# MA_interface-board.net
KiCad netlist of a schematic drawn in EAGLE
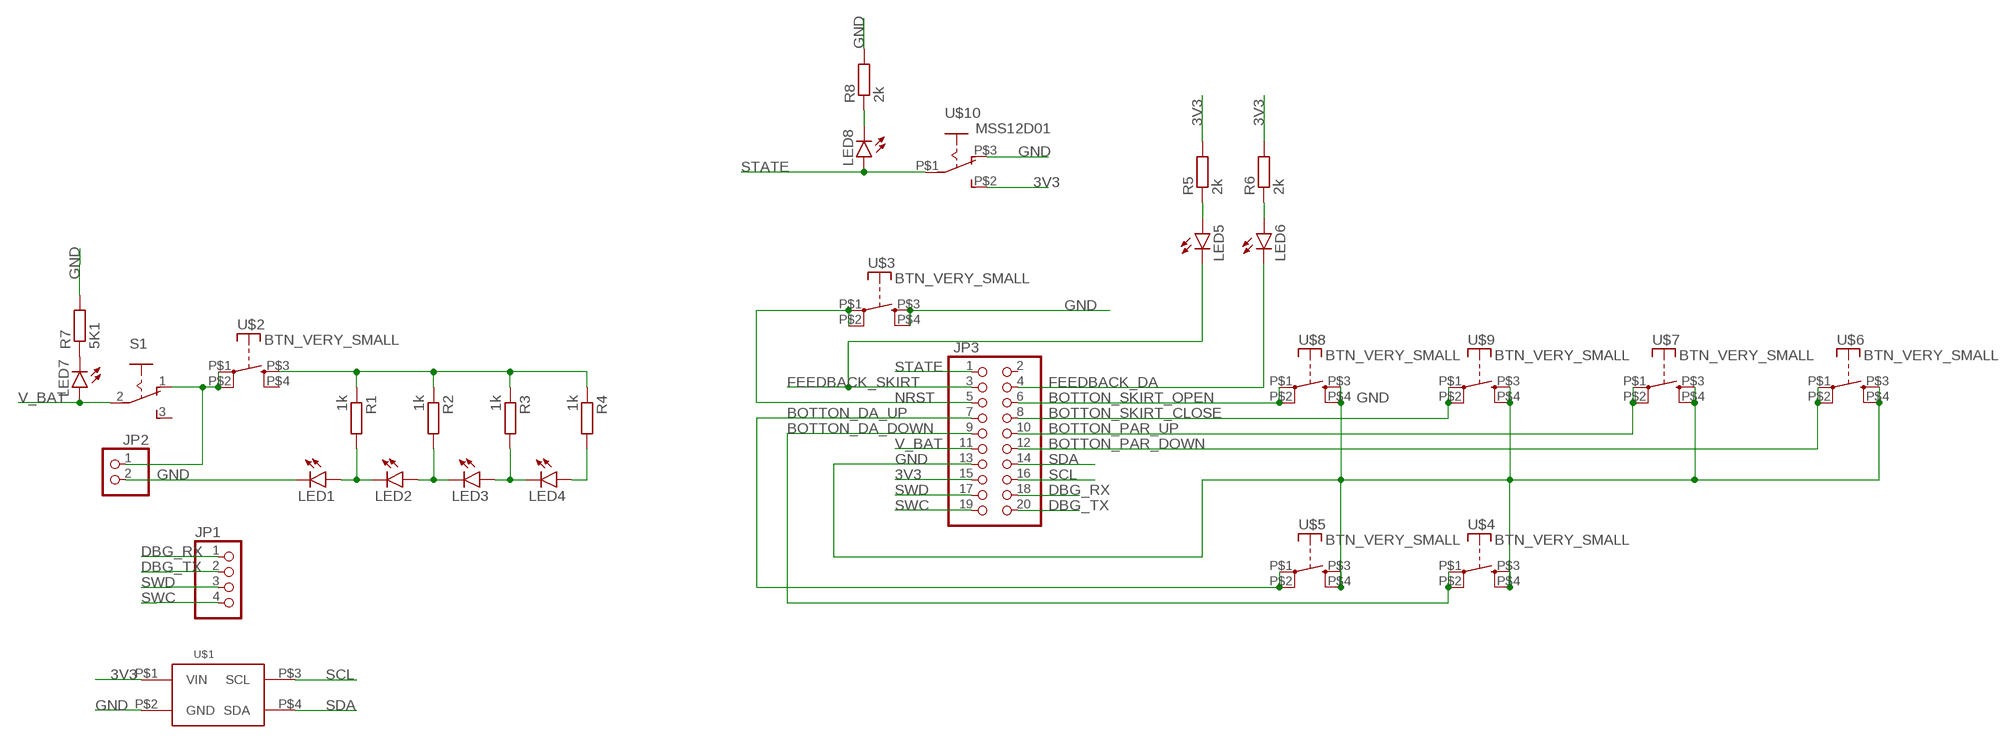
[diagram p0: schematic, sheet 1]

(export (version "E")
  (design (tool "Eeschema 10.0.6"))
  (components
    (comp (ref "JP1")
      (value "PINHD-1X4")
      (footprint "eagle-import:1X04")
      (libsource (lib "eagle-import") (part "PINHD-1X4"))
    )
    (comp (ref "JP2")
      (value "PINHD-1X2")
      (footprint "eagle-import:1X02")
      (libsource (lib "eagle-import") (part "PINHD-1X2"))
    )
    (comp (ref "JP3")
      (value "PINHD-2X10")
      (footprint "eagle-import:2X10")
      (libsource (lib "eagle-import") (part "PINHD-2X10"))
    )
    (comp (ref "LED1")
      (value "LEDSML0603")
      (footprint "eagle-import:SML0603")
      (libsource (lib "eagle-import") (part "LEDSML0603"))
    )
    (comp (ref "LED2")
      (value "LEDSML0603")
      (footprint "eagle-import:SML0603")
      (libsource (lib "eagle-import") (part "LEDSML0603"))
    )
    (comp (ref "LED3")
      (value "LEDSML0603")
      (footprint "eagle-import:SML0603")
      (libsource (lib "eagle-import") (part "LEDSML0603"))
    )
    (comp (ref "LED4")
      (value "LEDSML0603")
      (footprint "eagle-import:SML0603")
      (libsource (lib "eagle-import") (part "LEDSML0603"))
    )
    (comp (ref "LED5")
      (value "LEDSML0603")
      (footprint "eagle-import:SML0603")
      (libsource (lib "eagle-import") (part "LEDSML0603"))
    )
    (comp (ref "LED6")
      (value "LEDSML0603")
      (footprint "eagle-import:SML0603")
      (libsource (lib "eagle-import") (part "LEDSML0603"))
    )
    (comp (ref "LED7")
      (value "LEDSML0603")
      (footprint "eagle-import:SML0603")
      (libsource (lib "eagle-import") (part "LEDSML0603"))
    )
    (comp (ref "LED8")
      (value "LEDSML0603")
      (footprint "eagle-import:SML0603")
      (libsource (lib "eagle-import") (part "LEDSML0603"))
    )
    (comp (ref "R1")
      (value "1k")
      (footprint "eagle-import:R0603")
      (libsource (lib "eagle-import") (part "R-EU_R0603"))
    )
    (comp (ref "R2")
      (value "1k")
      (footprint "eagle-import:R0603")
      (libsource (lib "eagle-import") (part "R-EU_R0603"))
    )
    (comp (ref "R3")
      (value "1k")
      (footprint "eagle-import:R0603")
      (libsource (lib "eagle-import") (part "R-EU_R0603"))
    )
    (comp (ref "R4")
      (value "1k")
      (footprint "eagle-import:R0603")
      (libsource (lib "eagle-import") (part "R-EU_R0603"))
    )
    (comp (ref "R5")
      (value "2k")
      (footprint "eagle-import:R0603")
      (libsource (lib "eagle-import") (part "R-EU_R0603"))
    )
    (comp (ref "R6")
      (value "2k")
      (footprint "eagle-import:R0603")
      (libsource (lib "eagle-import") (part "R-EU_R0603"))
    )
    (comp (ref "R7")
      (value "5K1")
      (footprint "eagle-import:R0603")
      (libsource (lib "eagle-import") (part "R-EU_R0603"))
    )
    (comp (ref "R8")
      (value "2k")
      (footprint "eagle-import:R0603")
      (libsource (lib "eagle-import") (part "R-EU_R0603"))
    )
    (comp (ref "S1")
      (value "UNICS-SWITCH")
      (footprint "eagle-import:UNICS-SWITCH")
      (libsource (lib "eagle-import") (part "UNICS-SWITCH"))
    )
    (comp (ref "U$1")
      (value "BME280BME280-PINS-ONLY")
      (footprint "eagle-import:BME280-PINS-ONLY")
      (libsource (lib "eagle-import") (part "BME280BME280-PINS-ONLY"))
    )
    (comp (ref "U$2")
      (value "BTN_VERY_SMALL")
      (footprint "eagle-import:BTN_VERY_SMALL")
      (libsource (lib "eagle-import") (part "BTN_VERY_SMALL"))
    )
    (comp (ref "U$3")
      (value "BTN_VERY_SMALL")
      (footprint "eagle-import:BTN_VERY_SMALL")
      (libsource (lib "eagle-import") (part "BTN_VERY_SMALL"))
    )
    (comp (ref "U$4")
      (value "BTN_VERY_SMALL")
      (footprint "eagle-import:BTN_VERY_SMALL")
      (libsource (lib "eagle-import") (part "BTN_VERY_SMALL"))
    )
    (comp (ref "U$5")
      (value "BTN_VERY_SMALL")
      (footprint "eagle-import:BTN_VERY_SMALL")
      (libsource (lib "eagle-import") (part "BTN_VERY_SMALL"))
    )
    (comp (ref "U$6")
      (value "BTN_VERY_SMALL")
      (footprint "eagle-import:BTN_VERY_SMALL")
      (libsource (lib "eagle-import") (part "BTN_VERY_SMALL"))
    )
    (comp (ref "U$7")
      (value "BTN_VERY_SMALL")
      (footprint "eagle-import:BTN_VERY_SMALL")
      (libsource (lib "eagle-import") (part "BTN_VERY_SMALL"))
    )
    (comp (ref "U$8")
      (value "BTN_VERY_SMALL")
      (footprint "eagle-import:BTN_VERY_SMALL")
      (libsource (lib "eagle-import") (part "BTN_VERY_SMALL"))
    )
    (comp (ref "U$9")
      (value "BTN_VERY_SMALL")
      (footprint "eagle-import:BTN_VERY_SMALL")
      (libsource (lib "eagle-import") (part "BTN_VERY_SMALL"))
    )
    (comp (ref "U$10")
      (value "MSS12D01")
      (footprint "eagle-import:MSS12D01")
      (libsource (lib "eagle-import") (part "MSS12D01"))
    )
  )
  (nets
    (net (code "1") (name "/3V3") (class "Default")
      (node (ref "JP3") (pin "15") (pinfunction "15_15") (pintype "passive"))
      (node (ref "R5") (pin "2") (pinfunction "2_2") (pintype "passive"))
      (node (ref "R6") (pin "2") (pinfunction "2_2") (pintype "passive"))
      (node (ref "U$1") (pin "P$1") (pinfunction "VIN_P$1") (pintype "bidirectional"))
      (node (ref "U$10") (pin "P$2") (pinfunction "S_P$2") (pintype "passive"))
    )
    (net (code "2") (name "/BOTTON_DA_DOWN") (class "Default")
      (node (ref "JP3") (pin "9") (pinfunction "9_9") (pintype "passive"))
      (node (ref "U$4") (pin "P$1") (pinfunction "P_P$1") (pintype "passive"))
      (node (ref "U$4") (pin "P$2") (pinfunction "P_P$2") (pintype "passive"))
    )
    (net (code "3") (name "/BOTTON_DA_UP") (class "Default")
      (node (ref "JP3") (pin "7") (pinfunction "7_7") (pintype "passive"))
      (node (ref "U$5") (pin "P$1") (pinfunction "P_P$1") (pintype "passive"))
      (node (ref "U$5") (pin "P$2") (pinfunction "P_P$2") (pintype "passive"))
    )
    (net (code "4") (name "/BOTTON_PAR_DOWN") (class "Default")
      (node (ref "JP3") (pin "12") (pinfunction "12_12") (pintype "passive"))
      (node (ref "U$6") (pin "P$1") (pinfunction "P_P$1") (pintype "passive"))
      (node (ref "U$6") (pin "P$2") (pinfunction "P_P$2") (pintype "passive"))
    )
    (net (code "5") (name "/BOTTON_PAR_UP") (class "Default")
      (node (ref "JP3") (pin "10") (pinfunction "10_10") (pintype "passive"))
      (node (ref "U$7") (pin "P$1") (pinfunction "P_P$1") (pintype "passive"))
      (node (ref "U$7") (pin "P$2") (pinfunction "P_P$2") (pintype "passive"))
    )
    (net (code "6") (name "/BOTTON_SKIRT_CLOSE") (class "Default")
      (node (ref "JP3") (pin "8") (pinfunction "8_8") (pintype "passive"))
      (node (ref "U$9") (pin "P$1") (pinfunction "P_P$1") (pintype "passive"))
      (node (ref "U$9") (pin "P$2") (pinfunction "P_P$2") (pintype "passive"))
    )
    (net (code "7") (name "/BOTTON_SKIRT_OPEN") (class "Default")
      (node (ref "JP3") (pin "6") (pinfunction "6_6") (pintype "passive"))
      (node (ref "U$8") (pin "P$1") (pinfunction "P_P$1") (pintype "passive"))
      (node (ref "U$8") (pin "P$2") (pinfunction "P_P$2") (pintype "passive"))
    )
    (net (code "8") (name "/DBG_RX") (class "Default")
      (node (ref "JP1") (pin "1") (pinfunction "1_1") (pintype "passive"))
      (node (ref "JP3") (pin "18") (pinfunction "18_18") (pintype "passive"))
    )
    (net (code "9") (name "/DBG_TX") (class "Default")
      (node (ref "JP1") (pin "2") (pinfunction "2_2") (pintype "passive"))
      (node (ref "JP3") (pin "20") (pinfunction "20_20") (pintype "passive"))
    )
    (net (code "10") (name "/FEEDBACK_DA") (class "Default")
      (node (ref "JP3") (pin "4") (pinfunction "4_4") (pintype "passive"))
      (node (ref "LED6") (pin "C") (pinfunction "C_C") (pintype "passive"))
    )
    (net (code "11") (name "/FEEDBACK_SKIRT") (class "Default")
      (node (ref "JP3") (pin "3") (pinfunction "3_3") (pintype "passive"))
      (node (ref "LED5") (pin "C") (pinfunction "C_C") (pintype "passive"))
    )
    (net (code "12") (name "/GND") (class "Default")
      (node (ref "JP2") (pin "2") (pinfunction "2_2") (pintype "passive"))
      (node (ref "JP3") (pin "13") (pinfunction "13_13") (pintype "passive"))
      (node (ref "LED1") (pin "C") (pinfunction "C_C") (pintype "passive"))
      (node (ref "R7") (pin "2") (pinfunction "2_2") (pintype "passive"))
      (node (ref "R8") (pin "2") (pinfunction "2_2") (pintype "passive"))
      (node (ref "U$1") (pin "P$2") (pinfunction "GND_P$2") (pintype "bidirectional"))
      (node (ref "U$10") (pin "P$3") (pinfunction "O_P$3") (pintype "passive"))
      (node (ref "U$3") (pin "P$3") (pinfunction "S_P$3") (pintype "passive"))
      (node (ref "U$3") (pin "P$4") (pinfunction "S_P$4") (pintype "passive"))
      (node (ref "U$4") (pin "P$3") (pinfunction "S_P$3") (pintype "passive"))
      (node (ref "U$4") (pin "P$4") (pinfunction "S_P$4") (pintype "passive"))
      (node (ref "U$5") (pin "P$3") (pinfunction "S_P$3") (pintype "passive"))
      (node (ref "U$5") (pin "P$4") (pinfunction "S_P$4") (pintype "passive"))
      (node (ref "U$6") (pin "P$3") (pinfunction "S_P$3") (pintype "passive"))
      (node (ref "U$6") (pin "P$4") (pinfunction "S_P$4") (pintype "passive"))
      (node (ref "U$7") (pin "P$3") (pinfunction "S_P$3") (pintype "passive"))
      (node (ref "U$7") (pin "P$4") (pinfunction "S_P$4") (pintype "passive"))
      (node (ref "U$8") (pin "P$3") (pinfunction "S_P$3") (pintype "passive"))
      (node (ref "U$8") (pin "P$4") (pinfunction "S_P$4") (pintype "passive"))
      (node (ref "U$9") (pin "P$3") (pinfunction "S_P$3") (pintype "passive"))
      (node (ref "U$9") (pin "P$4") (pinfunction "S_P$4") (pintype "passive"))
    )
    (net (code "13") (name "/NRST") (class "Default")
      (node (ref "JP3") (pin "5") (pinfunction "5_5") (pintype "passive"))
      (node (ref "U$3") (pin "P$1") (pinfunction "P_P$1") (pintype "passive"))
      (node (ref "U$3") (pin "P$2") (pinfunction "P_P$2") (pintype "passive"))
    )
    (net (code "14") (name "/SCL") (class "Default")
      (node (ref "JP3") (pin "16") (pinfunction "16_16") (pintype "passive"))
      (node (ref "U$1") (pin "P$3") (pinfunction "SCL_P$3") (pintype "bidirectional"))
    )
    (net (code "15") (name "/SDA") (class "Default")
      (node (ref "JP3") (pin "14") (pinfunction "14_14") (pintype "passive"))
      (node (ref "U$1") (pin "P$4") (pinfunction "SDA_P$4") (pintype "bidirectional"))
    )
    (net (code "16") (name "/STATE") (class "Default")
      (node (ref "JP3") (pin "1") (pinfunction "1_1") (pintype "passive"))
      (node (ref "LED8") (pin "A") (pinfunction "A_A") (pintype "passive"))
      (node (ref "U$10") (pin "P$1") (pinfunction "P_P$1") (pintype "passive"))
    )
    (net (code "17") (name "/SWC") (class "Default")
      (node (ref "JP1") (pin "4") (pinfunction "4_4") (pintype "passive"))
      (node (ref "JP3") (pin "19") (pinfunction "19_19") (pintype "passive"))
    )
    (net (code "18") (name "/SWD") (class "Default")
      (node (ref "JP1") (pin "3") (pinfunction "3_3") (pintype "passive"))
      (node (ref "JP3") (pin "17") (pinfunction "17_17") (pintype "passive"))
    )
    (net (code "19") (name "/V_BAT") (class "Default")
      (node (ref "JP3") (pin "11") (pinfunction "11_11") (pintype "passive"))
      (node (ref "LED7") (pin "A") (pinfunction "A_A") (pintype "passive"))
      (node (ref "S1") (pin "2") (pinfunction "P_2") (pintype "passive"))
    )
    (net (code "20") (name "Net-(LED1-PadA)") (class "Default")
      (node (ref "LED1") (pin "A") (pinfunction "A_A") (pintype "passive"))
      (node (ref "LED2") (pin "C") (pinfunction "C_C") (pintype "passive"))
      (node (ref "R1") (pin "2") (pinfunction "2_2") (pintype "passive"))
    )
    (net (code "21") (name "Net-(LED2-PadA)") (class "Default")
      (node (ref "LED2") (pin "A") (pinfunction "A_A") (pintype "passive"))
      (node (ref "LED3") (pin "C") (pinfunction "C_C") (pintype "passive"))
      (node (ref "R2") (pin "2") (pinfunction "2_2") (pintype "passive"))
    )
    (net (code "22") (name "Net-(LED3-PadA)") (class "Default")
      (node (ref "LED3") (pin "A") (pinfunction "A_A") (pintype "passive"))
      (node (ref "LED4") (pin "C") (pinfunction "C_C") (pintype "passive"))
      (node (ref "R3") (pin "2") (pinfunction "2_2") (pintype "passive"))
    )
    (net (code "23") (name "Net-(LED4-PadA)") (class "Default")
      (node (ref "LED4") (pin "A") (pinfunction "A_A") (pintype "passive"))
      (node (ref "R4") (pin "2") (pinfunction "2_2") (pintype "passive"))
    )
    (net (code "24") (name "Net-(LED5-PadA)") (class "Default")
      (node (ref "LED5") (pin "A") (pinfunction "A_A") (pintype "passive"))
      (node (ref "R5") (pin "1") (pinfunction "1_1") (pintype "passive"))
    )
    (net (code "25") (name "Net-(LED6-PadA)") (class "Default")
      (node (ref "LED6") (pin "A") (pinfunction "A_A") (pintype "passive"))
      (node (ref "R6") (pin "1") (pinfunction "1_1") (pintype "passive"))
    )
    (net (code "26") (name "Net-(LED7-PadC)") (class "Default")
      (node (ref "LED7") (pin "C") (pinfunction "C_C") (pintype "passive"))
      (node (ref "R7") (pin "1") (pinfunction "1_1") (pintype "passive"))
    )
    (net (code "27") (name "Net-(LED8-PadC)") (class "Default")
      (node (ref "LED8") (pin "C") (pinfunction "C_C") (pintype "passive"))
      (node (ref "R8") (pin "1") (pinfunction "1_1") (pintype "passive"))
    )
    (net (code "28") (name "Net-(R1-Pad1)") (class "Default")
      (node (ref "R1") (pin "1") (pinfunction "1_1") (pintype "passive"))
      (node (ref "R2") (pin "1") (pinfunction "1_1") (pintype "passive"))
      (node (ref "R3") (pin "1") (pinfunction "1_1") (pintype "passive"))
      (node (ref "R4") (pin "1") (pinfunction "1_1") (pintype "passive"))
      (node (ref "U$2") (pin "P$3") (pinfunction "S_P$3") (pintype "passive"))
    )
    (net (code "29") (name "Net-(S1-O)") (class "Default")
      (node (ref "JP2") (pin "1") (pinfunction "1_1") (pintype "passive"))
      (node (ref "S1") (pin "1") (pinfunction "O_1") (pintype "passive"))
      (node (ref "U$2") (pin "P$1") (pinfunction "P_P$1") (pintype "passive"))
      (node (ref "U$2") (pin "P$2") (pinfunction "P_P$2") (pintype "passive"))
    )
    (net (code "30") (name "unconnected-(JP3-Pad2)") (class "Default")
      (node (ref "JP3") (pin "2") (pinfunction "2_2") (pintype "passive"))
    )
    (net (code "31") (name "unconnected-(S1-S-Pad3)") (class "Default")
      (node (ref "S1") (pin "3") (pinfunction "S_3") (pintype "passive"))
    )
    (net (code "32") (name "unconnected-(U$2-S-PadP$4)") (class "Default")
      (node (ref "U$2") (pin "P$4") (pinfunction "S_P$4") (pintype "passive"))
    )
  )
)
